# GMP_SCH.net
KiCad netlist of a schematic drawn in EAGLE
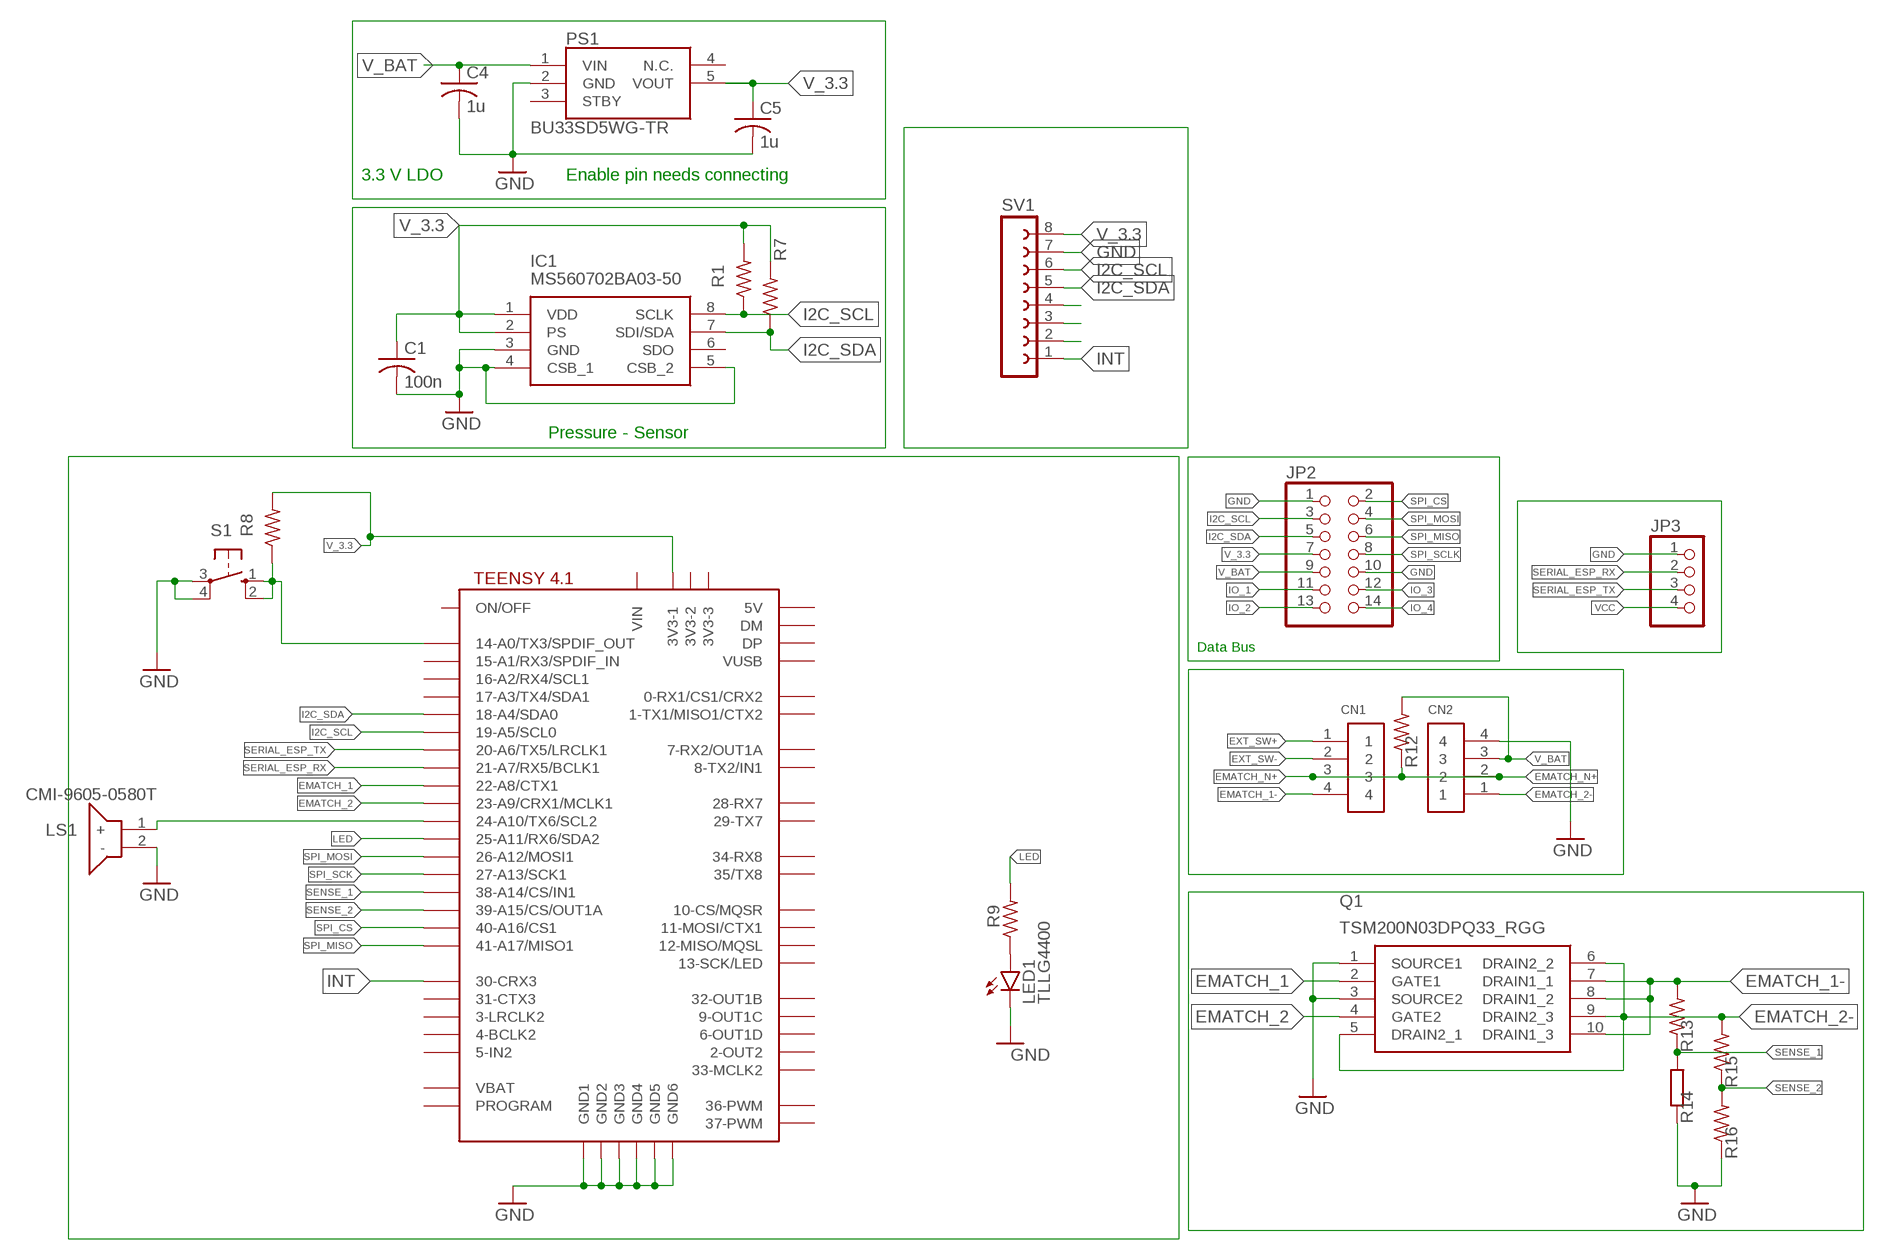
[diagram p0: schematic, sheet 1]

(export (version "E")
  (design (tool "Eeschema 10.0.6"))
  (components
    (comp (ref "C1")
      (value "100n")
      (footprint "eagle-import:C0805")
      (libsource (lib "eagle-import") (part "C-USC0805"))
    )
    (comp (ref "C4")
      (value "1u")
      (footprint "eagle-import:C0805")
      (libsource (lib "eagle-import") (part "C-USC0805"))
    )
    (comp (ref "C5")
      (value "1u")
      (footprint "eagle-import:C0805")
      (libsource (lib "eagle-import") (part "C-USC0805"))
    )
    (comp (ref "CN1")
      (value "1X4-3.5MM")
      (footprint "eagle-import:1X04-3.5MM")
      (libsource (lib "eagle-import") (part "1X4-3.5MM"))
    )
    (comp (ref "CN2")
      (value "1X4-3.5MM")
      (footprint "eagle-import:1X04-3.5MM")
      (libsource (lib "eagle-import") (part "1X4-3.5MM"))
    )
    (comp (ref "IC1")
      (value "MS560702BA03-50")
      (footprint "eagle-import:MS5607-02BA03")
      (fields (field (name "MOUSER_PART_NUMBER") "824-MS560702BA03-50"))
      (libsource (lib "eagle-import") (part "MS560702BA03-50"))
    )
    (comp (ref "JP2")
      (value "PINHD-2X7")
      (footprint "eagle-import:2X07")
      (libsource (lib "eagle-import") (part "PINHD-2X7"))
    )
    (comp (ref "JP3")
      (value "PINHD-1X4/90")
      (footprint "eagle-import:1X04_90")
      (libsource (lib "eagle-import") (part "PINHD-1X4/90"))
    )
    (comp (ref "LED1")
      (value "TLLG4400")
      (footprint "eagle-import:LED3MM")
      (fields (field (name "MF") "VISHAY SEMICONDUCTOR"))
      (libsource (lib "eagle-import") (part "TLLG4400"))
    )
    (comp (ref "LS1")
      (value "CMI-9605-0580T")
      (footprint "eagle-import:CMI96050580T")
      (fields (field (name "MOUSER_PART_NUMBER") "490-CMI-9605-0580T"))
      (libsource (lib "eagle-import") (part "CMI-9605-0580T"))
    )
    (comp (ref "PS1")
      (value "BU33SD5WG-TR")
      (footprint "eagle-import:SOT95P280X125-5N")
      (fields (field (name "MOUSER_PART_NUMBER") "755-BU33SD5WG-TR"))
      (libsource (lib "eagle-import") (part "BU33SD5WG-TR"))
    )
    (comp (ref "Q1")
      (value "TSM200N03DPQ33_RGG")
      (footprint "eagle-import:TSM200N03DPQ33RGG")
      (fields
        (field (name "MANUFACTURER_PART_NUMBER") "TSM200N03DPQ33 RGG")
        (field (name "MOUSER_PART_NUMBER") "821-TSM200N03DPQ33RG")
      )
      (libsource (lib "eagle-import") (part "TSM200N03DPQ33_RGG"))
    )
    (comp (ref "R1")
      (value "10k")
      (footprint "eagle-import:0805-THM")
      (libsource (lib "eagle-import") (part "FLIPFLOP-RES"))
    )
    (comp (ref "R7")
      (value "10k")
      (footprint "eagle-import:0805-THM")
      (libsource (lib "eagle-import") (part "FLIPFLOP-RES"))
    )
    (comp (ref "R8")
      (value "10k")
      (footprint "eagle-import:0805-THM")
      (libsource (lib "eagle-import") (part "FLIPFLOP-RES"))
    )
    (comp (ref "R9")
      (value "2k")
      (footprint "eagle-import:0805-THM")
      (libsource (lib "eagle-import") (part "FLIPFLOP-RES"))
    )
    (comp (ref "R12")
      (value "0")
      (footprint "eagle-import:0805-THM")
      (libsource (lib "eagle-import") (part "FLIPFLOP-RES"))
    )
    (comp (ref "R13")
      (value "100k")
      (footprint "eagle-import:0805-THM")
      (libsource (lib "eagle-import") (part "FLIPFLOP-RES"))
    )
    (comp (ref "R14")
      (value "27k")
      (footprint "eagle-import:0207_12")
      (libsource (lib "eagle-import") (part "R-EU_0207/12"))
    )
    (comp (ref "R15")
      (value "100k")
      (footprint "eagle-import:0805-THM")
      (libsource (lib "eagle-import") (part "FLIPFLOP-RES"))
    )
    (comp (ref "R16")
      (value "27k")
      (footprint "eagle-import:0805-THM")
      (libsource (lib "eagle-import") (part "FLIPFLOP-RES"))
    )
    (comp (ref "S1")
      (value "10-XX")
      (footprint "eagle-import:B3F-10XX")
      (fields (field (name "MPN") "B3F-1000"))
      (libsource (lib "eagle-import") (part "10-XX"))
    )
    (comp (ref "SV1")
      (value "FE08-1")
      (footprint "eagle-import:FE08")
      (libsource (lib "eagle-import") (part "FE08-1"))
    )
    (comp (ref "U$1")
      (value "TEENSY41-E")
      (footprint "eagle-import:TENNSY41-E")
      (libsource (lib "eagle-import") (part "TEENSY41-E"))
    )
  )
  (nets
    (net (code "1") (name "EMATCH_1") (class "Default")
      (node (ref "Q1") (pin "2") (pinfunction "GATE1_2") (pintype "bidirectional"))
      (node (ref "U$1") (pin "22-A8/CTX1") (pinfunction "22-A8/CTX1_22-A8/CTX1") (pintype "bidirectional"))
    )
    (net (code "2") (name "EMATCH_1-") (class "Default")
      (node (ref "CN1") (pin "4") (pinfunction "4_4") (pintype "bidirectional"))
      (node (ref "Q1") (pin "10") (pinfunction "DRAIN1_3_10") (pintype "bidirectional"))
      (node (ref "Q1") (pin "7") (pinfunction "DRAIN1_1_7") (pintype "bidirectional"))
      (node (ref "Q1") (pin "8") (pinfunction "DRAIN1_2_8") (pintype "bidirectional"))
      (node (ref "R13") (pin "2") (pinfunction "2_2") (pintype "passive"))
    )
    (net (code "3") (name "EMATCH_2") (class "Default")
      (node (ref "Q1") (pin "4") (pinfunction "GATE2_4") (pintype "bidirectional"))
      (node (ref "U$1") (pin "23-A9/CRX1/MCLK1") (pinfunction "23-A9/CRX1/MCLK1_23-A9/CRX1/MCLK1") (pintype "bidirectional"))
    )
    (net (code "4") (name "EMATCH_2-") (class "Default")
      (node (ref "CN2") (pin "1") (pinfunction "1_1") (pintype "bidirectional"))
      (node (ref "Q1") (pin "5") (pinfunction "DRAIN2_1_5") (pintype "bidirectional"))
      (node (ref "Q1") (pin "6") (pinfunction "DRAIN2_2_6") (pintype "bidirectional"))
      (node (ref "Q1") (pin "9") (pinfunction "DRAIN2_3_9") (pintype "bidirectional"))
      (node (ref "R15") (pin "2") (pinfunction "2_2") (pintype "passive"))
    )
    (net (code "5") (name "EMATCH_N+") (class "Default")
      (node (ref "CN1") (pin "3") (pinfunction "3_3") (pintype "bidirectional"))
      (node (ref "CN2") (pin "2") (pinfunction "2_2") (pintype "bidirectional"))
      (node (ref "R12") (pin "1") (pinfunction "1_1") (pintype "passive"))
    )
    (net (code "6") (name "EXT_SW+") (class "Default")
      (node (ref "CN1") (pin "1") (pinfunction "1_1") (pintype "bidirectional"))
    )
    (net (code "7") (name "EXT_SW-") (class "Default")
      (node (ref "CN1") (pin "2") (pinfunction "2_2") (pintype "bidirectional"))
    )
    (net (code "8") (name "GND") (class "Default")
      (node (ref "C1") (pin "2") (pinfunction "2_2") (pintype "passive"))
      (node (ref "C4") (pin "2") (pinfunction "2_2") (pintype "passive"))
      (node (ref "C5") (pin "2") (pinfunction "2_2") (pintype "passive"))
      (node (ref "CN2") (pin "4") (pinfunction "4_4") (pintype "bidirectional"))
      (node (ref "IC1") (pin "3") (pinfunction "GND_3") (pintype "power_in"))
      (node (ref "IC1") (pin "4") (pinfunction "CSB_1_4") (pintype "input"))
      (node (ref "IC1") (pin "5") (pinfunction "CSB_2_5") (pintype "input"))
      (node (ref "JP2") (pin "1") (pinfunction "1_1") (pintype "passive"))
      (node (ref "JP2") (pin "10") (pinfunction "10_10") (pintype "passive"))
      (node (ref "JP3") (pin "1") (pinfunction "1_1") (pintype "passive"))
      (node (ref "LED1") (pin "K") (pinfunction "C_K") (pintype "passive"))
      (node (ref "LS1") (pin "2") (pinfunction "-_2") (pintype "bidirectional"))
      (node (ref "PS1") (pin "2") (pinfunction "GND_2") (pintype "bidirectional"))
      (node (ref "Q1") (pin "1") (pinfunction "SOURCE1_1") (pintype "bidirectional"))
      (node (ref "Q1") (pin "3") (pinfunction "SOURCE2_3") (pintype "bidirectional"))
      (node (ref "R14") (pin "1") (pinfunction "1_1") (pintype "passive"))
      (node (ref "R16") (pin "1") (pinfunction "1_1") (pintype "passive"))
      (node (ref "S1") (pin "3") (pinfunction "P_3") (pintype "passive"))
      (node (ref "S1") (pin "4") (pinfunction "P1_4") (pintype "passive"))
      (node (ref "SV1") (pin "7") (pinfunction "7_7") (pintype "passive"))
      (node (ref "U$1") (pin "GND1") (pinfunction "GND1_GND1") (pintype "bidirectional"))
      (node (ref "U$1") (pin "GND2") (pinfunction "GND2_GND2") (pintype "bidirectional"))
      (node (ref "U$1") (pin "GND3") (pinfunction "GND3_GND3") (pintype "bidirectional"))
      (node (ref "U$1") (pin "GND4") (pinfunction "GND4_GND4") (pintype "bidirectional"))
      (node (ref "U$1") (pin "GND5") (pinfunction "GND5_GND5") (pintype "bidirectional"))
      (node (ref "U$1") (pin "GND6") (pinfunction "GND6_GND6") (pintype "bidirectional"))
    )
    (net (code "9") (name "I2C_SCL") (class "Default")
      (node (ref "IC1") (pin "8") (pinfunction "SCLK_8") (pintype "input"))
      (node (ref "JP2") (pin "3") (pinfunction "3_3") (pintype "passive"))
      (node (ref "R1") (pin "1") (pinfunction "1_1") (pintype "passive"))
      (node (ref "SV1") (pin "6") (pinfunction "6_6") (pintype "passive"))
      (node (ref "U$1") (pin "19-A5/SCL0") (pinfunction "19-A5/SCL0_19-A5/SCL0") (pintype "bidirectional"))
    )
    (net (code "10") (name "I2C_SDA") (class "Default")
      (node (ref "IC1") (pin "7") (pinfunction "SDI/SDA_7") (pintype "bidirectional"))
      (node (ref "JP2") (pin "5") (pinfunction "5_5") (pintype "passive"))
      (node (ref "R7") (pin "1") (pinfunction "1_1") (pintype "passive"))
      (node (ref "SV1") (pin "5") (pinfunction "5_5") (pintype "passive"))
      (node (ref "U$1") (pin "18-A4/SDA0") (pinfunction "18-A4/SDA0_18-A4/SDA0") (pintype "bidirectional"))
    )
    (net (code "11") (name "INT") (class "Default")
      (node (ref "SV1") (pin "1") (pinfunction "1_1") (pintype "passive"))
      (node (ref "U$1") (pin "30-CRX3") (pinfunction "30-CRX3_30-CRX3") (pintype "bidirectional"))
    )
    (net (code "12") (name "IO_1") (class "Default")
      (node (ref "JP2") (pin "11") (pinfunction "11_11") (pintype "passive"))
    )
    (net (code "13") (name "IO_2") (class "Default")
      (node (ref "JP2") (pin "13") (pinfunction "13_13") (pintype "passive"))
    )
    (net (code "14") (name "IO_3") (class "Default")
      (node (ref "JP2") (pin "12") (pinfunction "12_12") (pintype "passive"))
    )
    (net (code "15") (name "IO_4") (class "Default")
      (node (ref "JP2") (pin "14") (pinfunction "14_14") (pintype "passive"))
    )
    (net (code "16") (name "LED") (class "Default")
      (node (ref "R9") (pin "2") (pinfunction "2_2") (pintype "passive"))
      (node (ref "U$1") (pin "25-A11/RX6/SDA2") (pinfunction "25-A11/RX6/SDA2_25-A11/RX6/SDA2") (pintype "bidirectional"))
    )
    (net (code "17") (name "Net-(LED1-PadA)") (class "Default")
      (node (ref "LED1") (pin "A") (pinfunction "A_A") (pintype "passive"))
      (node (ref "R9") (pin "1") (pinfunction "1_1") (pintype "passive"))
    )
    (net (code "18") (name "Net-(LS1-+)") (class "Default")
      (node (ref "LS1") (pin "1") (pinfunction "+_1") (pintype "bidirectional"))
      (node (ref "U$1") (pin "24-A10/TX6/SCL2") (pinfunction "24-A10/TX6/SCL2_24-A10/TX6/SCL2") (pintype "bidirectional"))
    )
    (net (code "19") (name "Net-(S1-S)") (class "Default")
      (node (ref "R8") (pin "1") (pinfunction "1_1") (pintype "passive"))
      (node (ref "S1") (pin "1") (pinfunction "S_1") (pintype "passive"))
      (node (ref "S1") (pin "2") (pinfunction "S1_2") (pintype "passive"))
      (node (ref "U$1") (pin "14-A0/TX3/SPDIF_OUT") (pinfunction "14-A0/TX3/SPDIF_OUT_14-A0/TX3/SPDIF_OUT") (pintype "bidirectional"))
    )
    (net (code "20") (name "SENSE_1") (class "Default")
      (node (ref "R13") (pin "1") (pinfunction "1_1") (pintype "passive"))
      (node (ref "R14") (pin "2") (pinfunction "2_2") (pintype "passive"))
      (node (ref "U$1") (pin "38-A14/CS/IN1") (pinfunction "38-A14/CS/IN1_38-A14/CS/IN1") (pintype "bidirectional"))
    )
    (net (code "21") (name "SENSE_2") (class "Default")
      (node (ref "R15") (pin "1") (pinfunction "1_1") (pintype "passive"))
      (node (ref "R16") (pin "2") (pinfunction "2_2") (pintype "passive"))
      (node (ref "U$1") (pin "39-A15/CS/OUT1A") (pinfunction "39-A15/CS/OUT1A_39-A15/CS/OUT1A") (pintype "bidirectional"))
    )
    (net (code "22") (name "SERIAL_ESP_RX") (class "Default")
      (node (ref "JP3") (pin "2") (pinfunction "2_2") (pintype "passive"))
      (node (ref "U$1") (pin "21-A7/RX5/BCLK1") (pinfunction "21-A7/RX5/BCLK1_21-A7/RX5/BCLK1") (pintype "bidirectional"))
    )
    (net (code "23") (name "SERIAL_ESP_TX") (class "Default")
      (node (ref "JP3") (pin "3") (pinfunction "3_3") (pintype "passive"))
      (node (ref "U$1") (pin "20-A6/TX5/LRCLK1") (pinfunction "20-A6/TX5/LRCLK1_20-A6/TX5/LRCLK1") (pintype "bidirectional"))
    )
    (net (code "24") (name "SPI_CS") (class "Default")
      (node (ref "JP2") (pin "2") (pinfunction "2_2") (pintype "passive"))
      (node (ref "U$1") (pin "40-A16/CS1") (pinfunction "40-A16/CS1_40-A16/CS1") (pintype "bidirectional"))
    )
    (net (code "25") (name "SPI_MISO") (class "Default")
      (node (ref "JP2") (pin "6") (pinfunction "6_6") (pintype "passive"))
      (node (ref "U$1") (pin "41-A17/MISO1") (pinfunction "41-A17/MISO1_41-A17/MISO1") (pintype "bidirectional"))
    )
    (net (code "26") (name "SPI_MOSI") (class "Default")
      (node (ref "JP2") (pin "4") (pinfunction "4_4") (pintype "passive"))
      (node (ref "U$1") (pin "26-A12/MOSI1") (pinfunction "26-A12/MOSI1_26-A12/MOSI1") (pintype "bidirectional"))
    )
    (net (code "27") (name "SPI_SCK") (class "Default")
      (node (ref "U$1") (pin "27-A13/SCK1") (pinfunction "27-A13/SCK1_27-A13/SCK1") (pintype "bidirectional"))
    )
    (net (code "28") (name "SPI_SCLK") (class "Default")
      (node (ref "JP2") (pin "8") (pinfunction "8_8") (pintype "passive"))
    )
    (net (code "29") (name "VCC") (class "Default")
      (node (ref "JP3") (pin "4") (pinfunction "4_4") (pintype "passive"))
    )
    (net (code "30") (name "V_3.3") (class "Default")
      (node (ref "C1") (pin "1") (pinfunction "1_1") (pintype "passive"))
      (node (ref "C5") (pin "1") (pinfunction "1_1") (pintype "passive"))
      (node (ref "IC1") (pin "1") (pinfunction "VDD_1") (pintype "power_in"))
      (node (ref "IC1") (pin "2") (pinfunction "PS_2") (pintype "input"))
      (node (ref "JP2") (pin "7") (pinfunction "7_7") (pintype "passive"))
      (node (ref "PS1") (pin "5") (pinfunction "VOUT_5") (pintype "bidirectional"))
      (node (ref "R1") (pin "2") (pinfunction "2_2") (pintype "passive"))
      (node (ref "R7") (pin "2") (pinfunction "2_2") (pintype "passive"))
      (node (ref "R8") (pin "2") (pinfunction "2_2") (pintype "passive"))
      (node (ref "SV1") (pin "8") (pinfunction "8_8") (pintype "passive"))
      (node (ref "U$1") (pin "3V3-1") (pinfunction "3V3-1_3V3-1") (pintype "bidirectional"))
    )
    (net (code "31") (name "V_BAT") (class "Default")
      (node (ref "C4") (pin "1") (pinfunction "1_1") (pintype "passive"))
      (node (ref "CN2") (pin "3") (pinfunction "3_3") (pintype "bidirectional"))
      (node (ref "JP2") (pin "9") (pinfunction "9_9") (pintype "passive"))
      (node (ref "PS1") (pin "1") (pinfunction "VIN_1") (pintype "bidirectional"))
      (node (ref "R12") (pin "2") (pinfunction "2_2") (pintype "passive"))
    )
    (net (code "32") (name "unconnected-(IC1-SDO-Pad6)") (class "Default")
      (node (ref "IC1") (pin "6") (pinfunction "SDO_6") (pintype "output"))
    )
    (net (code "33") (name "unconnected-(PS1-N.C.-Pad4)") (class "Default")
      (node (ref "PS1") (pin "4") (pinfunction "N.C._4") (pintype "no_connect"))
    )
    (net (code "34") (name "unconnected-(PS1-STBY-Pad3)") (class "Default")
      (node (ref "PS1") (pin "3") (pinfunction "STBY_3") (pintype "bidirectional"))
    )
    (net (code "35") (name "unconnected-(SV1-Pad2)") (class "Default")
      (node (ref "SV1") (pin "2") (pinfunction "2_2") (pintype "passive"))
    )
    (net (code "36") (name "unconnected-(SV1-Pad3)") (class "Default")
      (node (ref "SV1") (pin "3") (pinfunction "3_3") (pintype "passive"))
    )
    (net (code "37") (name "unconnected-(SV1-Pad4)") (class "Default")
      (node (ref "SV1") (pin "4") (pinfunction "4_4") (pintype "passive"))
    )
    (net (code "38") (name "unconnected-(U$1-5V-Pad+5V)") (class "Default")
      (node (ref "U$1") (pin "+5V") (pinfunction "5V_+5V") (pintype "bidirectional"))
    )
    (net (code "39") (name "unconnected-(U$1-10-CS{slash}MQSR-Pad10-CS\\MQSR)") (class "Default")
      (node (ref "U$1") (pin "10-CS\\MQSR") (pinfunction "10-CS/MQSR_10-CS\\MQSR") (pintype "bidirectional"))
    )
    (net (code "40") (name "unconnected-(U$1-35{slash}TX8-Pad35-TX8)") (class "Default")
      (node (ref "U$1") (pin "35-TX8") (pinfunction "35/TX8_35-TX8") (pintype "bidirectional"))
    )
    (net (code "41") (name "unconnected-(U$1-Pad0-RX1{slash}CS1{slash}CRX2)") (class "Default")
      (node (ref "U$1") (pin "0-RX1/CS1/CRX2") (pinfunction "0-RX1/CS1/CRX2_0-RX1/CS1/CRX2") (pintype "bidirectional"))
    )
    (net (code "42") (name "unconnected-(U$1-Pad1-TX1{slash}MISO1{slash}CTX2)") (class "Default")
      (node (ref "U$1") (pin "1-TX1/MISO1/CTX2") (pinfunction "1-TX1/MISO1/CTX2_1-TX1/MISO1/CTX2") (pintype "bidirectional"))
    )
    (net (code "43") (name "unconnected-(U$1-Pad2-OUT2)") (class "Default")
      (node (ref "U$1") (pin "2-OUT2") (pinfunction "2-OUT2_2-OUT2") (pintype "bidirectional"))
    )
    (net (code "44") (name "unconnected-(U$1-Pad3-LRCLK2)") (class "Default")
      (node (ref "U$1") (pin "3-LRCLK2") (pinfunction "3-LRCLK2_3-LRCLK2") (pintype "bidirectional"))
    )
    (net (code "45") (name "unconnected-(U$1-Pad3V3-2)") (class "Default")
      (node (ref "U$1") (pin "3V3-2") (pinfunction "3V3-2_3V3-2") (pintype "bidirectional"))
    )
    (net (code "46") (name "unconnected-(U$1-Pad3V3-3)") (class "Default")
      (node (ref "U$1") (pin "3V3-3") (pinfunction "3V3-3_3V3-3") (pintype "bidirectional"))
    )
    (net (code "47") (name "unconnected-(U$1-Pad4-BCLK2)") (class "Default")
      (node (ref "U$1") (pin "4-BCLK2") (pinfunction "4-BCLK2_4-BCLK2") (pintype "bidirectional"))
    )
    (net (code "48") (name "unconnected-(U$1-Pad5-IN2)") (class "Default")
      (node (ref "U$1") (pin "5-IN2") (pinfunction "5-IN2_5-IN2") (pintype "bidirectional"))
    )
    (net (code "49") (name "unconnected-(U$1-Pad6-OUT1D)") (class "Default")
      (node (ref "U$1") (pin "6-OUT1D") (pinfunction "6-OUT1D_6-OUT1D") (pintype "bidirectional"))
    )
    (net (code "50") (name "unconnected-(U$1-Pad7-RX2{slash}OUT1A)") (class "Default")
      (node (ref "U$1") (pin "7-RX2/OUT1A") (pinfunction "7-RX2/OUT1A_7-RX2/OUT1A") (pintype "bidirectional"))
    )
    (net (code "51") (name "unconnected-(U$1-Pad8-TX2{slash}IN1)") (class "Default")
      (node (ref "U$1") (pin "8-TX2/IN1") (pinfunction "8-TX2/IN1_8-TX2/IN1") (pintype "bidirectional"))
    )
    (net (code "52") (name "unconnected-(U$1-Pad9-OUT1C)") (class "Default")
      (node (ref "U$1") (pin "9-OUT1C") (pinfunction "9-OUT1C_9-OUT1C") (pintype "bidirectional"))
    )
    (net (code "53") (name "unconnected-(U$1-Pad11-MOSI{slash}CTX1)") (class "Default")
      (node (ref "U$1") (pin "11-MOSI/CTX1") (pinfunction "11-MOSI/CTX1_11-MOSI/CTX1") (pintype "bidirectional"))
    )
    (net (code "54") (name "unconnected-(U$1-Pad12-MISO{slash}MQSL)") (class "Default")
      (node (ref "U$1") (pin "12-MISO/MQSL") (pinfunction "12-MISO/MQSL_12-MISO/MQSL") (pintype "bidirectional"))
    )
    (net (code "55") (name "unconnected-(U$1-Pad13-SCK{slash}LED)") (class "Default")
      (node (ref "U$1") (pin "13-SCK/LED") (pinfunction "13-SCK/LED_13-SCK/LED") (pintype "bidirectional"))
    )
    (net (code "56") (name "unconnected-(U$1-Pad15-A1{slash}RX3{slash}SPDIF_IN)") (class "Default")
      (node (ref "U$1") (pin "15-A1/RX3/SPDIF_IN") (pinfunction "15-A1/RX3/SPDIF_IN_15-A1/RX3/SPDIF_IN") (pintype "bidirectional"))
    )
    (net (code "57") (name "unconnected-(U$1-Pad16-A2{slash}RX4{slash}SCL1)") (class "Default")
      (node (ref "U$1") (pin "16-A2/RX4/SCL1") (pinfunction "16-A2/RX4/SCL1_16-A2/RX4/SCL1") (pintype "bidirectional"))
    )
    (net (code "58") (name "unconnected-(U$1-Pad17-A3{slash}TX4{slash}SDA1)") (class "Default")
      (node (ref "U$1") (pin "17-A3/TX4/SDA1") (pinfunction "17-A3/TX4/SDA1_17-A3/TX4/SDA1") (pintype "bidirectional"))
    )
    (net (code "59") (name "unconnected-(U$1-Pad28-RX7)") (class "Default")
      (node (ref "U$1") (pin "28-RX7") (pinfunction "28-RX7_28-RX7") (pintype "bidirectional"))
    )
    (net (code "60") (name "unconnected-(U$1-Pad29-TX7)") (class "Default")
      (node (ref "U$1") (pin "29-TX7") (pinfunction "29-TX7_29-TX7") (pintype "bidirectional"))
    )
    (net (code "61") (name "unconnected-(U$1-Pad31-CTX3)") (class "Default")
      (node (ref "U$1") (pin "31-CTX3") (pinfunction "31-CTX3_31-CTX3") (pintype "bidirectional"))
    )
    (net (code "62") (name "unconnected-(U$1-Pad32-OUT1B)") (class "Default")
      (node (ref "U$1") (pin "32-OUT1B") (pinfunction "32-OUT1B_32-OUT1B") (pintype "bidirectional"))
    )
    (net (code "63") (name "unconnected-(U$1-Pad33-MCLK2)") (class "Default")
      (node (ref "U$1") (pin "33-MCLK2") (pinfunction "33-MCLK2_33-MCLK2") (pintype "bidirectional"))
    )
    (net (code "64") (name "unconnected-(U$1-Pad34-RX8)") (class "Default")
      (node (ref "U$1") (pin "34-RX8") (pinfunction "34-RX8_34-RX8") (pintype "bidirectional"))
    )
    (net (code "65") (name "unconnected-(U$1-Pad36-PWM)") (class "Default")
      (node (ref "U$1") (pin "36-PWM") (pinfunction "36-PWM_36-PWM") (pintype "bidirectional"))
    )
    (net (code "66") (name "unconnected-(U$1-Pad37-PWM)") (class "Default")
      (node (ref "U$1") (pin "37-PWM") (pinfunction "37-PWM_37-PWM") (pintype "bidirectional"))
    )
    (net (code "67") (name "unconnected-(U$1-PadDM)") (class "Default")
      (node (ref "U$1") (pin "DM") (pinfunction "DM_DM") (pintype "bidirectional"))
    )
    (net (code "68") (name "unconnected-(U$1-PadDP)") (class "Default")
      (node (ref "U$1") (pin "DP") (pinfunction "DP_DP") (pintype "bidirectional"))
    )
    (net (code "69") (name "unconnected-(U$1-PadON{slash}OFF)") (class "Default")
      (node (ref "U$1") (pin "ON/OFF") (pinfunction "ON/OFF_ON/OFF") (pintype "bidirectional"))
    )
    (net (code "70") (name "unconnected-(U$1-PadPROGRAM)") (class "Default")
      (node (ref "U$1") (pin "PROGRAM") (pinfunction "PROGRAM_PROGRAM") (pintype "bidirectional"))
    )
    (net (code "71") (name "unconnected-(U$1-PadVBAT)") (class "Default")
      (node (ref "U$1") (pin "VBAT") (pinfunction "VBAT_VBAT") (pintype "bidirectional"))
    )
    (net (code "72") (name "unconnected-(U$1-PadVIN)") (class "Default")
      (node (ref "U$1") (pin "VIN") (pinfunction "VIN_VIN") (pintype "bidirectional"))
    )
    (net (code "73") (name "unconnected-(U$1-PadVUSB)") (class "Default")
      (node (ref "U$1") (pin "VUSB") (pinfunction "VUSB_VUSB") (pintype "bidirectional"))
    )
  )
)
